# LOXpixel.net
KiCad netlist of a schematic drawn in EAGLE
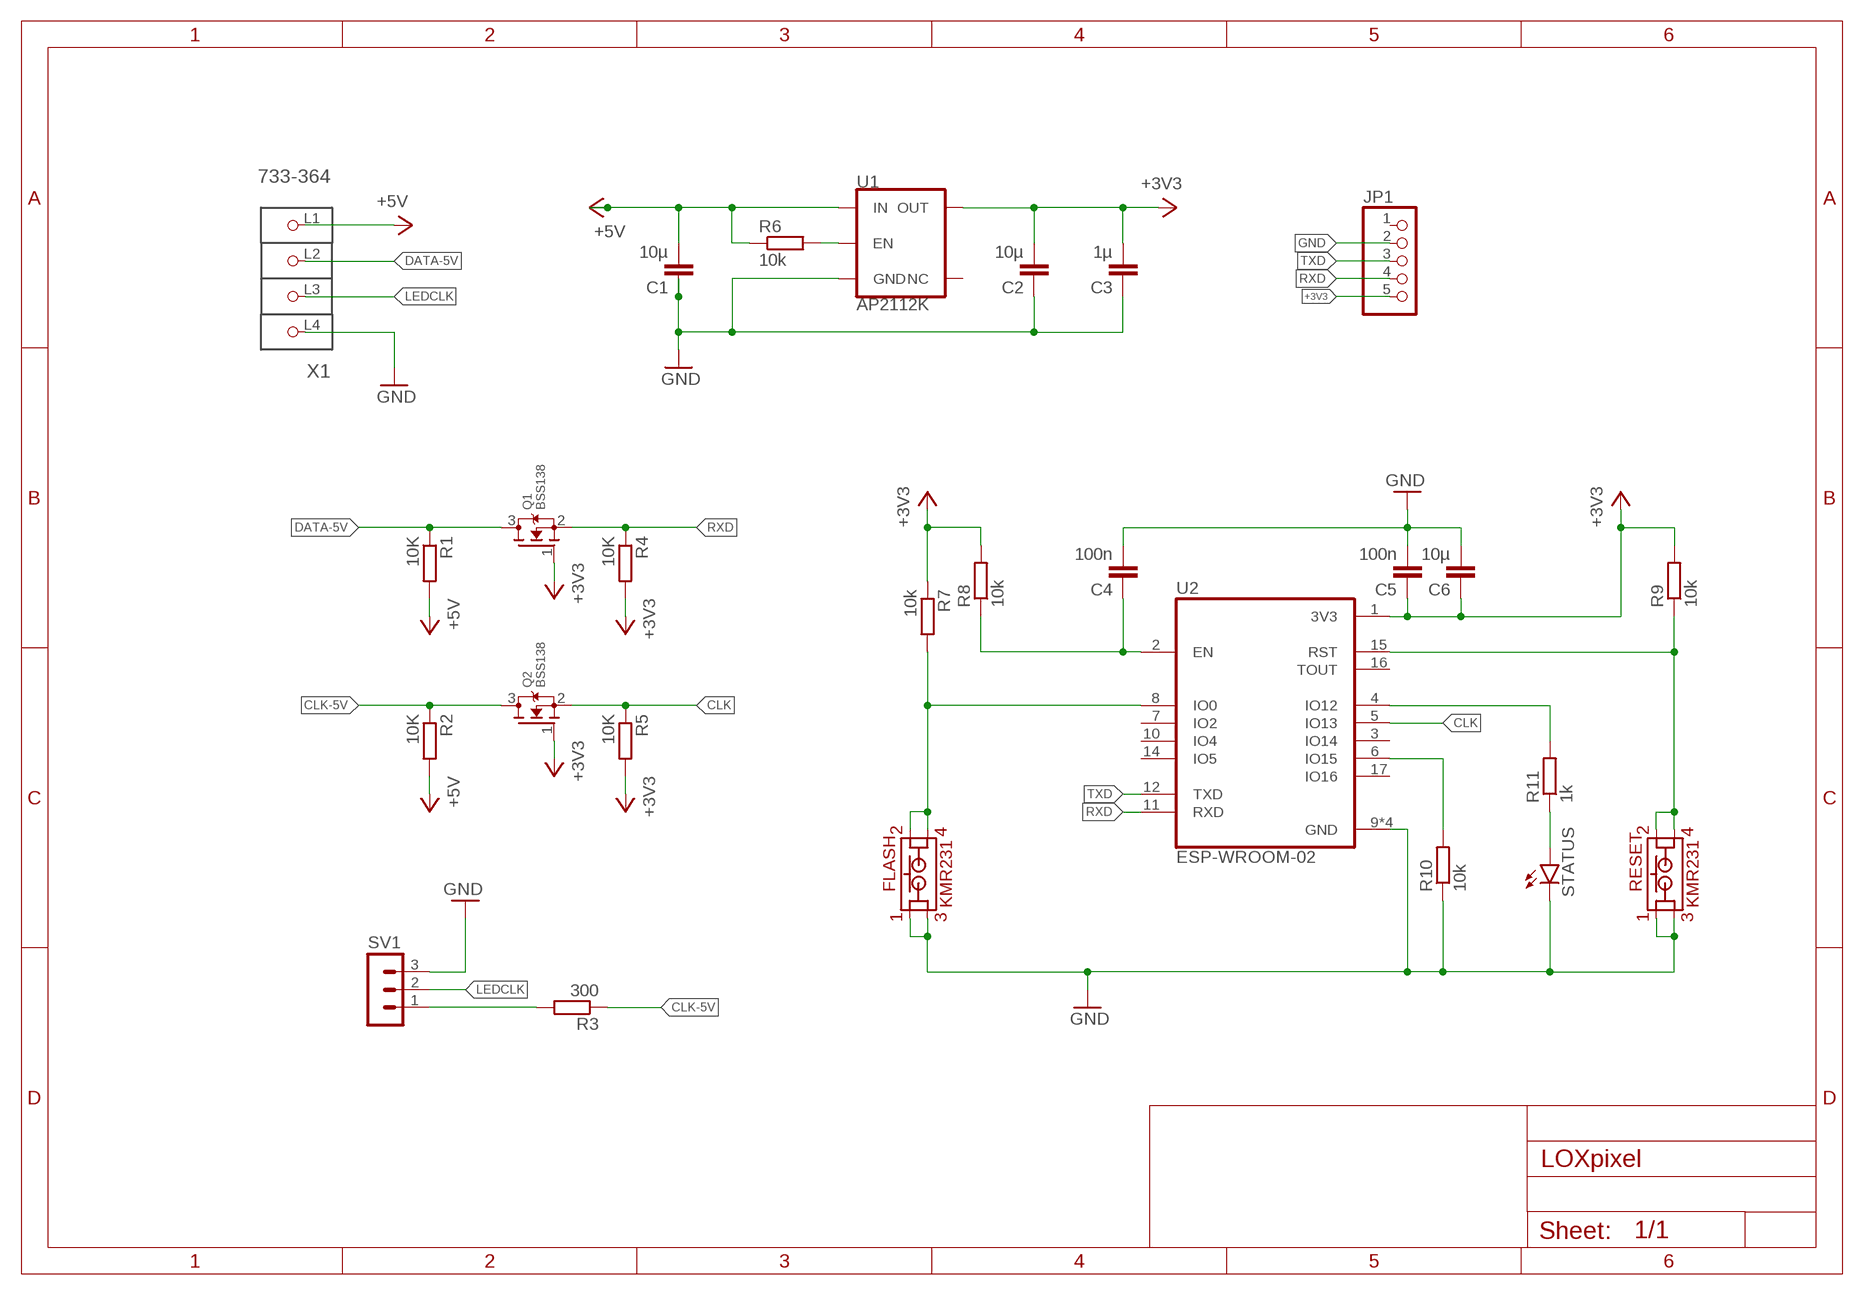
[diagram p0: schematic, sheet 1]

(export (version "E")
  (design (tool "Eeschema 10.0.6"))
  (components
    (comp (ref "C1")
      (value "10µ")
      (footprint "eagle-import:C0805")
      (libsource (lib "eagle-import") (part "C-EUC0805"))
    )
    (comp (ref "C2")
      (value "10µ")
      (footprint "eagle-import:C0805")
      (libsource (lib "eagle-import") (part "C-EUC0805"))
    )
    (comp (ref "C3")
      (value "1µ")
      (footprint "eagle-import:C0805")
      (libsource (lib "eagle-import") (part "C-EUC0805"))
    )
    (comp (ref "C4")
      (value "100n")
      (footprint "eagle-import:C0805")
      (libsource (lib "eagle-import") (part "C-EUC0805"))
    )
    (comp (ref "C5")
      (value "100n")
      (footprint "eagle-import:C0805")
      (libsource (lib "eagle-import") (part "C-EUC0805"))
    )
    (comp (ref "C6")
      (value "10µ")
      (footprint "eagle-import:C0805")
      (libsource (lib "eagle-import") (part "C-EUC0805"))
    )
    (comp (ref "FLASH")
      (value "KMR231")
      (footprint "eagle-import:GLFS")
      (libsource (lib "eagle-import") (part "KMR231"))
    )
    (comp (ref "JP1")
      (value "PINHD-1X5")
      (footprint "eagle-import:1X05")
      (libsource (lib "eagle-import") (part "PINHD-1X5"))
    )
    (comp (ref "Q1")
      (value "BSS138")
      (footprint "eagle-import:SOT23")
      (libsource (lib "eagle-import") (part "MOSFET-NREFLOW"))
    )
    (comp (ref "Q2")
      (value "BSS138")
      (footprint "eagle-import:SOT23")
      (libsource (lib "eagle-import") (part "MOSFET-NREFLOW"))
    )
    (comp (ref "R1")
      (value "10K")
      (footprint "eagle-import:R0805")
      (libsource (lib "eagle-import") (part "R-EU_R0805"))
    )
    (comp (ref "R2")
      (value "10K")
      (footprint "eagle-import:R0805")
      (libsource (lib "eagle-import") (part "R-EU_R0805"))
    )
    (comp (ref "R3")
      (value "300")
      (footprint "eagle-import:R0805")
      (libsource (lib "eagle-import") (part "R-EU_R0805"))
    )
    (comp (ref "R4")
      (value "10K")
      (footprint "eagle-import:R0805")
      (libsource (lib "eagle-import") (part "R-EU_R0805"))
    )
    (comp (ref "R5")
      (value "10K")
      (footprint "eagle-import:R0805")
      (libsource (lib "eagle-import") (part "R-EU_R0805"))
    )
    (comp (ref "R6")
      (value "10k")
      (footprint "eagle-import:R0805")
      (libsource (lib "eagle-import") (part "R-EU_R0805"))
    )
    (comp (ref "R7")
      (value "10k")
      (footprint "eagle-import:R0805")
      (libsource (lib "eagle-import") (part "R-EU_R0805"))
    )
    (comp (ref "R8")
      (value "10k")
      (footprint "eagle-import:R0805")
      (libsource (lib "eagle-import") (part "R-EU_R0805"))
    )
    (comp (ref "R9")
      (value "10k")
      (footprint "eagle-import:R0805")
      (libsource (lib "eagle-import") (part "R-EU_R0805"))
    )
    (comp (ref "R10")
      (value "10k")
      (footprint "eagle-import:R0805")
      (libsource (lib "eagle-import") (part "R-EU_R0805"))
    )
    (comp (ref "R11")
      (value "1k")
      (footprint "eagle-import:R0805")
      (libsource (lib "eagle-import") (part "R-EU_R0805"))
    )
    (comp (ref "RESET")
      (value "KMR231")
      (footprint "eagle-import:GLFS")
      (libsource (lib "eagle-import") (part "KMR231"))
    )
    (comp (ref "STATUS")
      (value "LEDCHIPLED_0805")
      (footprint "eagle-import:CHIPLED_0805")
      (libsource (lib "eagle-import") (part "LEDCHIPLED_0805"))
    )
    (comp (ref "SV1")
      (value "MA03-1")
      (footprint "eagle-import:MA03-1")
      (libsource (lib "eagle-import") (part "MA03-1"))
    )
    (comp (ref "U1")
      (value "AP2112K")
      (footprint "eagle-import:SOT23-5")
      (libsource (lib "eagle-import") (part "V_REG_AP2112K-3.3V"))
    )
    (comp (ref "U2")
      (value "ESP-WROOM-02")
      (footprint "eagle-import:MODULE_ESP-WROOM-02")
      (fields (field (name "MF") "Espressif Systems"))
      (libsource (lib "eagle-import") (part "ESP-WROOM-02"))
    )
    (comp (ref "X1")
      (value "733-364")
      (footprint "eagle-import:P-733-364")
      (libsource (lib "eagle-import") (part "733-364"))
    )
  )
  (nets
    (net (code "1") (name "+3V3") (class "Default")
      (node (ref "C2") (pin "2") (pinfunction "2_2") (pintype "passive"))
      (node (ref "C3") (pin "2") (pinfunction "2_2") (pintype "passive"))
      (node (ref "C5") (pin "1") (pinfunction "1_1") (pintype "passive"))
      (node (ref "C6") (pin "1") (pinfunction "1_1") (pintype "passive"))
      (node (ref "JP1") (pin "5") (pinfunction "5_5") (pintype "passive"))
      (node (ref "Q1") (pin "1") (pinfunction "G_1") (pintype "bidirectional"))
      (node (ref "Q2") (pin "1") (pinfunction "G_1") (pintype "bidirectional"))
      (node (ref "R4") (pin "2") (pinfunction "2_2") (pintype "passive"))
      (node (ref "R5") (pin "2") (pinfunction "2_2") (pintype "passive"))
      (node (ref "R7") (pin "1") (pinfunction "1_1") (pintype "passive"))
      (node (ref "R8") (pin "2") (pinfunction "2_2") (pintype "passive"))
      (node (ref "R9") (pin "2") (pinfunction "2_2") (pintype "passive"))
      (node (ref "U1") (pin "5") (pinfunction "OUT_5") (pintype "passive"))
      (node (ref "U2") (pin "1") (pinfunction "3V3_1") (pintype "power_in"))
    )
    (net (code "2") (name "+5V") (class "Default")
      (node (ref "C1") (pin "2") (pinfunction "2_2") (pintype "passive"))
      (node (ref "R1") (pin "2") (pinfunction "2_2") (pintype "passive"))
      (node (ref "R2") (pin "2") (pinfunction "2_2") (pintype "passive"))
      (node (ref "R6") (pin "1") (pinfunction "1_1") (pintype "passive"))
      (node (ref "U1") (pin "1") (pinfunction "IN_1") (pintype "input"))
      (node (ref "X1") (pin "L1") (pinfunction "P1_L1") (pintype "bidirectional"))
    )
    (net (code "3") (name "CLK") (class "Default")
      (node (ref "Q2") (pin "2") (pinfunction "S_2") (pintype "bidirectional"))
      (node (ref "R5") (pin "1") (pinfunction "1_1") (pintype "passive"))
      (node (ref "U2") (pin "5") (pinfunction "IO13_5") (pintype "bidirectional"))
    )
    (net (code "4") (name "CLK-5V") (class "Default")
      (node (ref "Q2") (pin "3") (pinfunction "D_3") (pintype "bidirectional"))
      (node (ref "R2") (pin "1") (pinfunction "1_1") (pintype "passive"))
      (node (ref "R3") (pin "1") (pinfunction "1_1") (pintype "passive"))
    )
    (net (code "5") (name "DATA-5V") (class "Default")
      (node (ref "Q1") (pin "3") (pinfunction "D_3") (pintype "bidirectional"))
      (node (ref "R1") (pin "1") (pinfunction "1_1") (pintype "passive"))
      (node (ref "X1") (pin "L2") (pinfunction "P2_L2") (pintype "bidirectional"))
    )
    (net (code "6") (name "GND") (class "Default")
      (node (ref "C1") (pin "1") (pinfunction "1_1") (pintype "passive"))
      (node (ref "C2") (pin "1") (pinfunction "1_1") (pintype "passive"))
      (node (ref "C3") (pin "1") (pinfunction "1_1") (pintype "passive"))
      (node (ref "C4") (pin "2") (pinfunction "2_2") (pintype "passive"))
      (node (ref "C5") (pin "2") (pinfunction "2_2") (pintype "passive"))
      (node (ref "C6") (pin "2") (pinfunction "2_2") (pintype "passive"))
      (node (ref "FLASH") (pin "P$1") (pinfunction "1_P$1") (pintype "bidirectional"))
      (node (ref "FLASH") (pin "P$3") (pinfunction "3_P$3") (pintype "bidirectional"))
      (node (ref "JP1") (pin "2") (pinfunction "2_2") (pintype "passive"))
      (node (ref "R10") (pin "1") (pinfunction "1_1") (pintype "passive"))
      (node (ref "RESET") (pin "P$1") (pinfunction "1_P$1") (pintype "bidirectional"))
      (node (ref "RESET") (pin "P$3") (pinfunction "3_P$3") (pintype "bidirectional"))
      (node (ref "STATUS") (pin "C") (pinfunction "C_C") (pintype "passive"))
      (node (ref "SV1") (pin "3") (pinfunction "3_3") (pintype "passive"))
      (node (ref "U1") (pin "2") (pinfunction "GND_2") (pintype "input"))
      (node (ref "U2") (pin "13") (pinfunction "GND_13") (pintype "power_in"))
      (node (ref "U2") (pin "18") (pinfunction "GND_18") (pintype "power_in"))
      (node (ref "U2") (pin "19") (pinfunction "GND_19") (pintype "power_in"))
      (node (ref "U2") (pin "9") (pinfunction "GND_9") (pintype "power_in"))
      (node (ref "X1") (pin "L4") (pinfunction "P4_L4") (pintype "bidirectional"))
    )
    (net (code "7") (name "LEDCLK") (class "Default")
      (node (ref "SV1") (pin "2") (pinfunction "2_2") (pintype "passive"))
      (node (ref "X1") (pin "L3") (pinfunction "P3_L3") (pintype "bidirectional"))
    )
    (net (code "8") (name "Net-(FLASH-2)") (class "Default")
      (node (ref "FLASH") (pin "P$2") (pinfunction "2_P$2") (pintype "bidirectional"))
      (node (ref "FLASH") (pin "P$4") (pinfunction "4_P$4") (pintype "bidirectional"))
      (node (ref "R7") (pin "2") (pinfunction "2_2") (pintype "passive"))
      (node (ref "U2") (pin "8") (pinfunction "IO0_8") (pintype "bidirectional"))
    )
    (net (code "9") (name "Net-(R3-Pad2)") (class "Default")
      (node (ref "R3") (pin "2") (pinfunction "2_2") (pintype "passive"))
      (node (ref "SV1") (pin "1") (pinfunction "1_1") (pintype "passive"))
    )
    (net (code "10") (name "Net-(R11-Pad1)") (class "Default")
      (node (ref "R11") (pin "1") (pinfunction "1_1") (pintype "passive"))
      (node (ref "STATUS") (pin "A") (pinfunction "A_A") (pintype "passive"))
    )
    (net (code "11") (name "Net-(RESET-2)") (class "Default")
      (node (ref "R9") (pin "1") (pinfunction "1_1") (pintype "passive"))
      (node (ref "RESET") (pin "P$2") (pinfunction "2_P$2") (pintype "bidirectional"))
      (node (ref "RESET") (pin "P$4") (pinfunction "4_P$4") (pintype "bidirectional"))
      (node (ref "U2") (pin "15") (pinfunction "RST_15") (pintype "bidirectional"))
    )
    (net (code "12") (name "Net-(U1-EN)") (class "Default")
      (node (ref "R6") (pin "2") (pinfunction "2_2") (pintype "passive"))
      (node (ref "U1") (pin "3") (pinfunction "EN_3") (pintype "input"))
    )
    (net (code "13") (name "Net-(U2-EN)") (class "Default")
      (node (ref "C4") (pin "1") (pinfunction "1_1") (pintype "passive"))
      (node (ref "R8") (pin "1") (pinfunction "1_1") (pintype "passive"))
      (node (ref "U2") (pin "2") (pinfunction "EN_2") (pintype "input"))
    )
    (net (code "14") (name "Net-(U2-IO12)") (class "Default")
      (node (ref "R11") (pin "2") (pinfunction "2_2") (pintype "passive"))
      (node (ref "U2") (pin "4") (pinfunction "IO12_4") (pintype "bidirectional"))
    )
    (net (code "15") (name "Net-(U2-IO15)") (class "Default")
      (node (ref "R10") (pin "2") (pinfunction "2_2") (pintype "passive"))
      (node (ref "U2") (pin "6") (pinfunction "IO15_6") (pintype "bidirectional"))
    )
    (net (code "16") (name "RXD") (class "Default")
      (node (ref "JP1") (pin "4") (pinfunction "4_4") (pintype "passive"))
      (node (ref "Q1") (pin "2") (pinfunction "S_2") (pintype "bidirectional"))
      (node (ref "R4") (pin "1") (pinfunction "1_1") (pintype "passive"))
      (node (ref "U2") (pin "11") (pinfunction "RXD_11") (pintype "bidirectional"))
    )
    (net (code "17") (name "TXD") (class "Default")
      (node (ref "JP1") (pin "3") (pinfunction "3_3") (pintype "passive"))
      (node (ref "U2") (pin "12") (pinfunction "TXD_12") (pintype "bidirectional"))
    )
    (net (code "18") (name "unconnected-(JP1-Pad1)") (class "Default")
      (node (ref "JP1") (pin "1") (pinfunction "1_1") (pintype "passive"))
    )
    (net (code "19") (name "unconnected-(U1-NC-Pad4)") (class "Default")
      (node (ref "U1") (pin "4") (pinfunction "NC_4") (pintype "no_connect"))
    )
    (net (code "20") (name "unconnected-(U2-IO2-Pad7)") (class "Default")
      (node (ref "U2") (pin "7") (pinfunction "IO2_7") (pintype "bidirectional"))
    )
    (net (code "21") (name "unconnected-(U2-IO4-Pad10)") (class "Default")
      (node (ref "U2") (pin "10") (pinfunction "IO4_10") (pintype "bidirectional"))
    )
    (net (code "22") (name "unconnected-(U2-IO5-Pad14)") (class "Default")
      (node (ref "U2") (pin "14") (pinfunction "IO5_14") (pintype "open_collector"))
    )
    (net (code "23") (name "unconnected-(U2-IO14-Pad3)") (class "Default")
      (node (ref "U2") (pin "3") (pinfunction "IO14_3") (pintype "bidirectional"))
    )
    (net (code "24") (name "unconnected-(U2-IO16-Pad17)") (class "Default")
      (node (ref "U2") (pin "17") (pinfunction "IO16_17") (pintype "bidirectional"))
    )
    (net (code "25") (name "unconnected-(U2-TOUT-Pad16)") (class "Default")
      (node (ref "U2") (pin "16") (pinfunction "TOUT_16") (pintype "bidirectional"))
    )
  )
)
